# Nixieclock.net
KiCad netlist of a schematic drawn in EAGLE
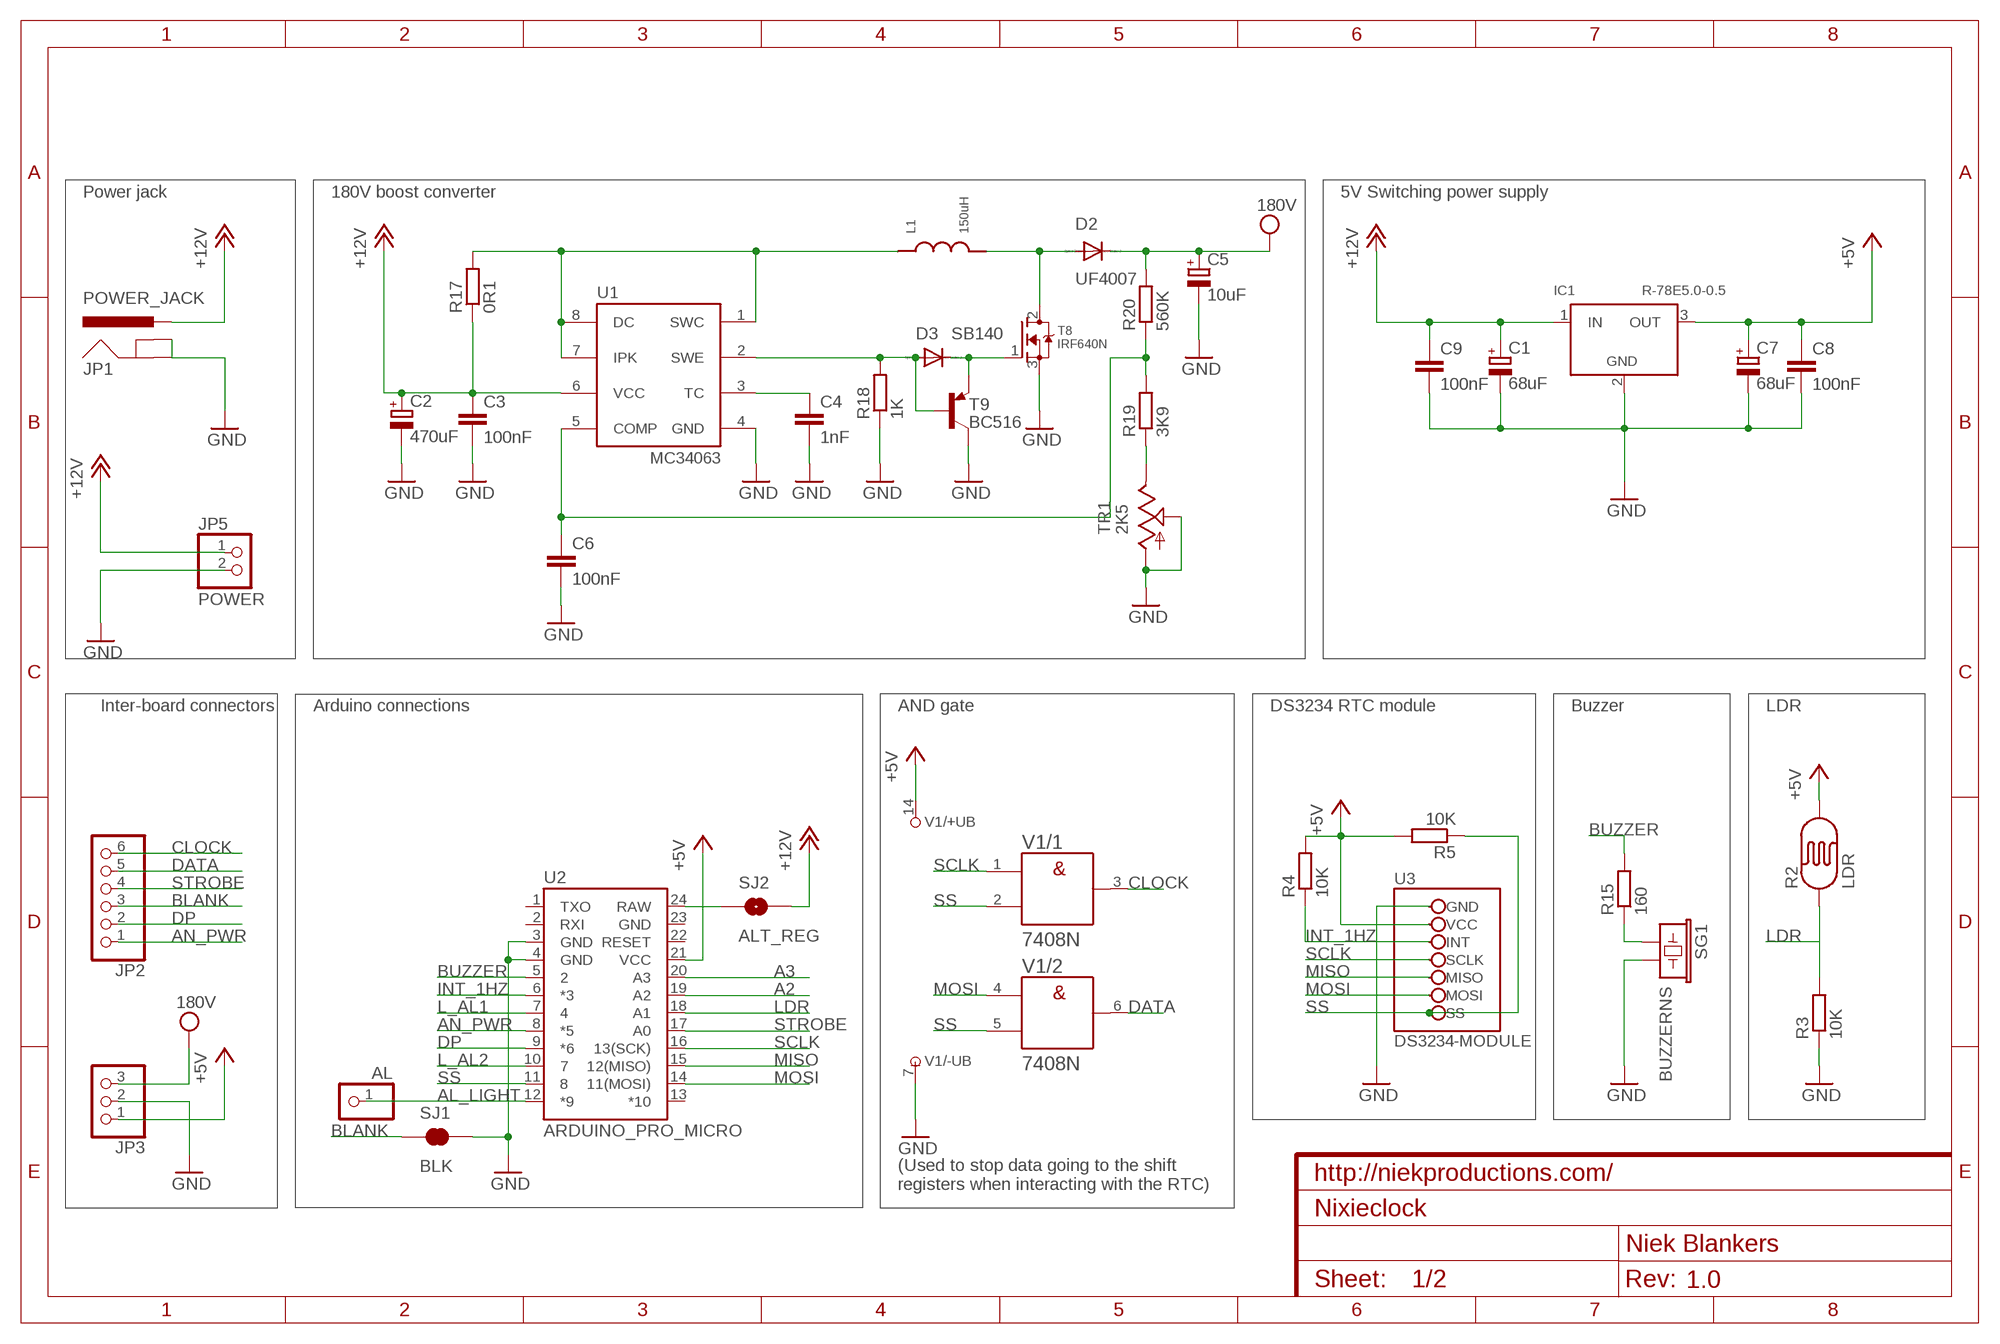
[diagram p0: schematic, sheet 1]
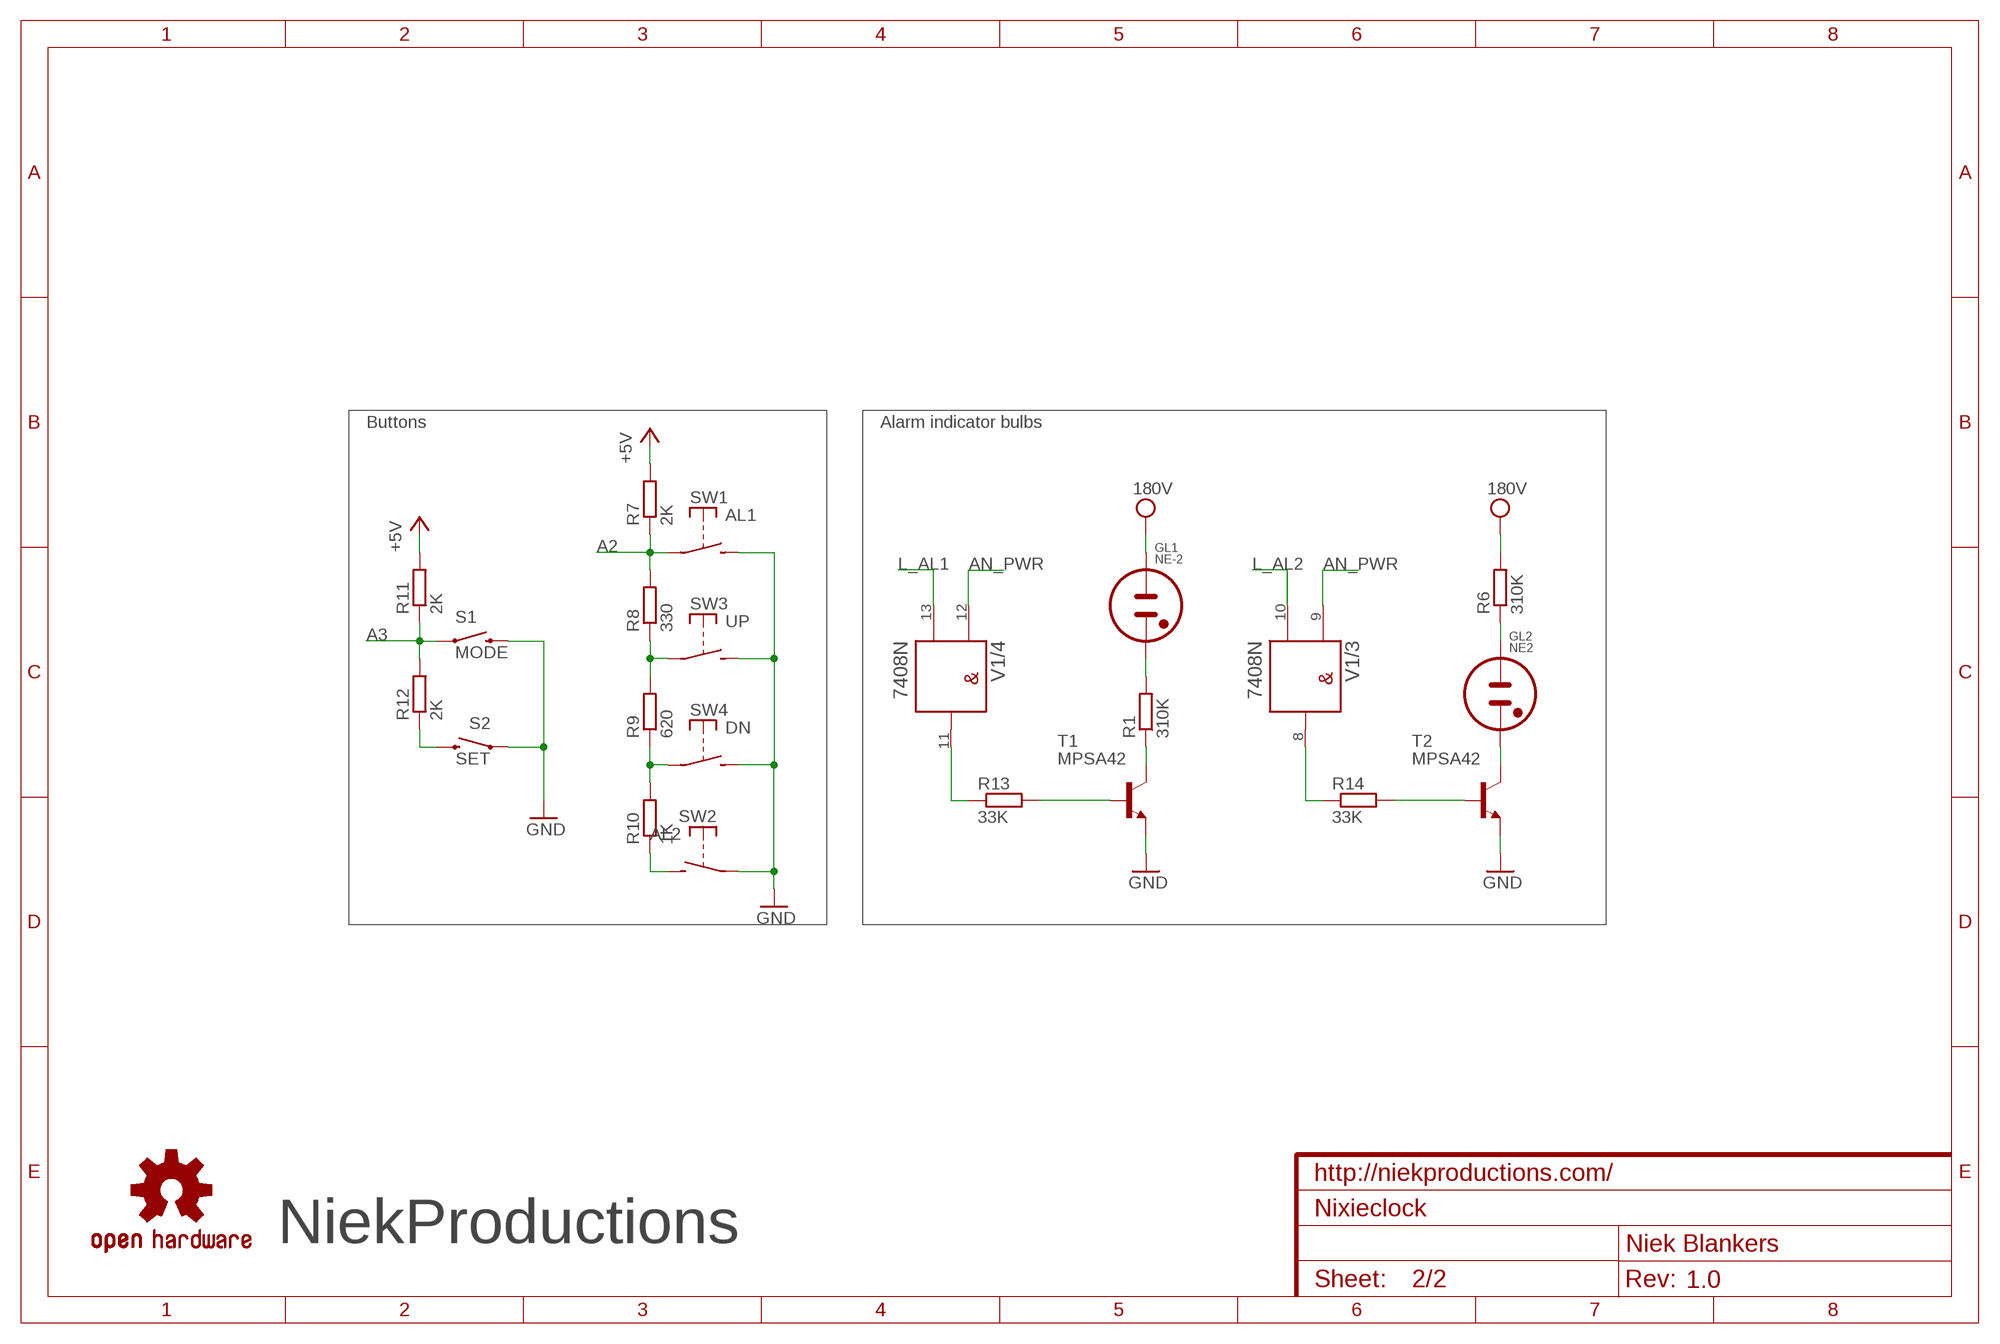
[diagram p1: schematic, sheet 2]

(export (version "E")
  (design (tool "Eeschema 10.0.6"))
  (components
    (comp (ref "AL")
      (value "PINHD-1X1")
      (footprint "eagle-import:1X01")
      (libsource (lib "eagle-import") (part "PINHD-1X1"))
    )
    (comp (ref "C1")
      (value "68uF")
      (footprint "eagle-import:E2,5-6")
      (libsource (lib "eagle-import") (part "CPOL-EUE2.5-6"))
    )
    (comp (ref "C2")
      (value "470uF")
      (footprint "eagle-import:E5-10,5")
      (libsource (lib "eagle-import") (part "CPOL-EUE5-10.5"))
    )
    (comp (ref "C3")
      (value "100nF")
      (footprint "eagle-import:C025-024X044")
      (libsource (lib "eagle-import") (part "C-EU025-024X044"))
    )
    (comp (ref "C4")
      (value "1nF")
      (footprint "eagle-import:C025-024X044")
      (libsource (lib "eagle-import") (part "C-EU025-024X044"))
    )
    (comp (ref "C5")
      (value "10uF")
      (footprint "eagle-import:E5-10,5")
      (libsource (lib "eagle-import") (part "CPOL-EUE5-10.5"))
    )
    (comp (ref "C6")
      (value "100nF")
      (footprint "eagle-import:C025-024X044")
      (libsource (lib "eagle-import") (part "C-EU025-024X044"))
    )
    (comp (ref "C7")
      (value "68uF")
      (footprint "eagle-import:E2,5-6")
      (libsource (lib "eagle-import") (part "CPOL-EUE2.5-6"))
    )
    (comp (ref "C8")
      (value "100nF")
      (footprint "eagle-import:C025-025X050")
      (libsource (lib "eagle-import") (part "C-EU025-025X050"))
    )
    (comp (ref "C9")
      (value "100nF")
      (footprint "eagle-import:C025-025X050")
      (libsource (lib "eagle-import") (part "C-EU025-025X050"))
    )
    (comp (ref "D2")
      (value "UF4007")
      (footprint "eagle-import:DO41-10")
      (libsource (lib "eagle-import") (part "1N4933"))
    )
    (comp (ref "D3")
      (value "SB140")
      (footprint "eagle-import:DO41-10")
      (libsource (lib "eagle-import") (part "1N4004"))
    )
    (comp (ref "IC1")
      (value "R-78E5.0-0.5")
      (footprint "eagle-import:R-78E")
      (libsource (lib "eagle-import") (part "R-78E5.0-0.5"))
    )
    (comp (ref "JP1")
      (value "POWER_JACK")
      (footprint "eagle-import:POWER_JACK_PTH_LOCK")
      (libsource (lib "eagle-import") (part "POWER_JACKPTH_LOCK"))
    )
    (comp (ref "JP2")
      (value "PINHD-1X6")
      (footprint "eagle-import:1X06")
      (libsource (lib "eagle-import") (part "PINHD-1X6"))
    )
    (comp (ref "JP3")
      (value "PINHD-1X3")
      (footprint "eagle-import:1X03")
      (libsource (lib "eagle-import") (part "PINHD-1X3"))
    )
    (comp (ref "JP5")
      (value "POWER")
      (footprint "eagle-import:1X02")
      (libsource (lib "eagle-import") (part "PINHD-1X2"))
    )
    (comp (ref "L1")
      (value "150uH")
      (footprint "eagle-import:INDUCTOR")
      (libsource (lib "eagle-import") (part "INDUCTOR"))
    )
    (comp (ref "R2")
      (value "LDR")
      (footprint "eagle-import:PHOTOCELL")
      (libsource (lib "eagle-import") (part "PHOTOCELLPTH"))
    )
    (comp (ref "R3")
      (value "10K")
      (footprint "eagle-import:0204_7")
      (libsource (lib "eagle-import") (part "R-EU_0204/7"))
    )
    (comp (ref "R4")
      (value "10K")
      (footprint "eagle-import:0204_7")
      (libsource (lib "eagle-import") (part "R-EU_0204/7"))
    )
    (comp (ref "R5")
      (value "10K")
      (footprint "eagle-import:0204_7")
      (libsource (lib "eagle-import") (part "R-EU_0204/7"))
    )
    (comp (ref "R15")
      (value "160")
      (footprint "eagle-import:0204_7")
      (libsource (lib "eagle-import") (part "R-EU_0204/7"))
    )
    (comp (ref "R17")
      (value "0R1")
      (footprint "eagle-import:0309_12")
      (libsource (lib "eagle-import") (part "R-EU_0309/12"))
    )
    (comp (ref "R18")
      (value "1K")
      (footprint "eagle-import:0207_10")
      (libsource (lib "eagle-import") (part "R-EU_0207/10"))
    )
    (comp (ref "R19")
      (value "3K9")
      (footprint "eagle-import:0207_10")
      (libsource (lib "eagle-import") (part "R-EU_0207/10"))
    )
    (comp (ref "R20")
      (value "560K")
      (footprint "eagle-import:0207_10")
      (libsource (lib "eagle-import") (part "R-EU_0207/10"))
    )
    (comp (ref "SG1")
      (value "BUZZERNS")
      (footprint "eagle-import:BUZZER-12MM-NS")
      (libsource (lib "eagle-import") (part "BUZZERNS"))
    )
    (comp (ref "SJ1")
      (value "BLK")
      (footprint "eagle-import:PAD-JUMPER-2-NC_BY_TRACE_YES_SILK")
      (libsource (lib "eagle-import") (part "JUMPER-PAD-2-NC_BY_TRACE"))
    )
    (comp (ref "SJ2")
      (value "ALT_REG")
      (footprint "eagle-import:SJ_2S-NO")
      (libsource (lib "eagle-import") (part "SOLDERJUMPERNO"))
    )
    (comp (ref "T8")
      (value "IRF640N")
      (footprint "eagle-import:TO220V")
      (libsource (lib "eagle-import") (part "MOSFET-NGDS_TO220V"))
    )
    (comp (ref "T9")
      (value "BC516")
      (footprint "eagle-import:TO92-EBC")
      (libsource (lib "eagle-import") (part "BC516"))
    )
    (comp (ref "TR1")
      (value "2K5")
      (footprint "eagle-import:6MM")
      (libsource (lib "eagle-import") (part "TRIM"))
    )
    (comp (ref "U1")
      (value "MC34063")
      (footprint "eagle-import:DIL08")
      (libsource (lib "eagle-import") (part "MC33063/MC34063P"))
    )
    (comp (ref "U2")
      (value "ARDUINO_PRO_MICRO")
      (footprint "eagle-import:ARDUINO_PRO_MICRO")
      (libsource (lib "eagle-import") (part "ARDUINO_PRO_MICRO"))
    )
    (comp (ref "U3")
      (value "DS3234-MODULE")
      (footprint "eagle-import:GEETECH-DS3234")
      (libsource (lib "eagle-import") (part "DS3234-MODULE"))
    )
    (comp (ref "V1")
      (value "7408N")
      (footprint "eagle-import:DIL14")
      (libsource (lib "eagle-import") (part "7408N"))
    )
    (comp (ref "GL1")
      (value "NE-2")
      (footprint "eagle-import:NE2-NEON-BULB-DRILL")
      (libsource (lib "eagle-import") (part "NE2-NEON-BULB-DRILL"))
    )
    (comp (ref "GL2")
      (value "NE2")
      (footprint "eagle-import:NE2-NEON-BULB-DRILL")
      (libsource (lib "eagle-import") (part "NE2-NEON-BULB-DRILL"))
    )
    (comp (ref "LOGO2")
      (value "OSHW-LOGOL")
      (footprint "eagle-import:OSHW-LOGO-L")
      (libsource (lib "eagle-import") (part "OSHW-LOGOL"))
    )
    (comp (ref "R1")
      (value "310K")
      (footprint "eagle-import:0204V")
      (libsource (lib "eagle-import") (part "R-EU_0204/2V"))
    )
    (comp (ref "R6")
      (value "310K")
      (footprint "eagle-import:0204_7")
      (libsource (lib "eagle-import") (part "R-EU_0204/7"))
    )
    (comp (ref "R7")
      (value "2K")
      (footprint "eagle-import:0204_7")
      (libsource (lib "eagle-import") (part "R-EU_0204/7"))
    )
    (comp (ref "R8")
      (value "330")
      (footprint "eagle-import:0204V")
      (libsource (lib "eagle-import") (part "R-EU_0204/2V"))
    )
    (comp (ref "R9")
      (value "620")
      (footprint "eagle-import:0204V")
      (libsource (lib "eagle-import") (part "R-EU_0204/2V"))
    )
    (comp (ref "R10")
      (value "1K")
      (footprint "eagle-import:0204V")
      (libsource (lib "eagle-import") (part "R-EU_0204/2V"))
    )
    (comp (ref "R11")
      (value "2K")
      (footprint "eagle-import:0204_7")
      (libsource (lib "eagle-import") (part "R-EU_0204/7"))
    )
    (comp (ref "R12")
      (value "2K")
      (footprint "eagle-import:0204_7")
      (libsource (lib "eagle-import") (part "R-EU_0204/7"))
    )
    (comp (ref "R13")
      (value "33K")
      (footprint "eagle-import:0204_7")
      (libsource (lib "eagle-import") (part "R-EU_0204/7"))
    )
    (comp (ref "R14")
      (value "33K")
      (footprint "eagle-import:0204_7")
      (libsource (lib "eagle-import") (part "R-EU_0204/7"))
    )
    (comp (ref "S1")
      (value "MODE")
      (footprint "eagle-import:TACTILE-PTH-SIDEEZ")
      (libsource (lib "eagle-import") (part "SWITCH-MOMENTARY-2SIDE_EZ"))
    )
    (comp (ref "S2")
      (value "SET")
      (footprint "eagle-import:TACTILE-PTH-SIDEEZ")
      (libsource (lib "eagle-import") (part "SWITCH-MOMENTARY-2SIDE_EZ"))
    )
    (comp (ref "SW1")
      (value "AL1")
      (footprint "eagle-import:SW-12.65MM-SQ-WHITE")
      (libsource (lib "eagle-import") (part "TACTILE-SQ12.65MM-WHITE"))
    )
    (comp (ref "SW2")
      (value "AL2")
      (footprint "eagle-import:SW-12.65MM-SQ-WHITE")
      (libsource (lib "eagle-import") (part "TACTILE-SQ12.65MM-WHITE"))
    )
    (comp (ref "SW3")
      (value "UP")
      (footprint "eagle-import:SW-12.65MM-SQ-WHITE")
      (libsource (lib "eagle-import") (part "TACTILE-SQ12.65MM-WHITE"))
    )
    (comp (ref "SW4")
      (value "DN")
      (footprint "eagle-import:SW-12.65MM-SQ-WHITE")
      (libsource (lib "eagle-import") (part "TACTILE-SQ12.65MM-WHITE"))
    )
    (comp (ref "T1")
      (value "MPSA42")
      (footprint "eagle-import:TO92-EBC")
      (libsource (lib "eagle-import") (part "-NPN-TO92-EBCMPSA42"))
    )
    (comp (ref "T2")
      (value "MPSA42")
      (footprint "eagle-import:TO92-EBC")
      (libsource (lib "eagle-import") (part "-NPN-TO92-EBCMPSA42"))
    )
    (comp (ref "U$4")
      (value "NPLOGO1CM-DIA")
      (footprint "eagle-import:NPLOGO-1CM")
      (libsource (lib "eagle-import") (part "NPLOGO1CM-DIA"))
    )
  )
  (nets
    (net (code "1") (name "+5V") (class "Default")
      (node (ref "C7") (pin "+") (pinfunction "+_+") (pintype "passive"))
      (node (ref "C8") (pin "1") (pinfunction "1_1") (pintype "passive"))
      (node (ref "IC1") (pin "3") (pinfunction "OUT_3") (pintype "output"))
      (node (ref "JP3") (pin "1") (pinfunction "1_1") (pintype "passive"))
      (node (ref "R11") (pin "2") (pinfunction "2_2") (pintype "passive"))
      (node (ref "R2") (pin "2") (pinfunction "P$2_2") (pintype "bidirectional"))
      (node (ref "R4") (pin "2") (pinfunction "2_2") (pintype "passive"))
      (node (ref "R5") (pin "2") (pinfunction "2_2") (pintype "passive"))
      (node (ref "R7") (pin "2") (pinfunction "2_2") (pintype "passive"))
      (node (ref "U2") (pin "21") (pinfunction "VCC_21") (pintype "bidirectional"))
      (node (ref "U3") (pin "VCC") (pinfunction "VCC_VCC") (pintype "input"))
      (node (ref "V1") (pin "14") (pinfunction "+UB_14") (pintype "power_in"))
    )
    (net (code "2") (name "+12V") (class "Default")
      (node (ref "C1") (pin "+") (pinfunction "+_+") (pintype "passive"))
      (node (ref "C2") (pin "+") (pinfunction "+_+") (pintype "passive"))
      (node (ref "C3") (pin "1") (pinfunction "1_1") (pintype "passive"))
      (node (ref "C9") (pin "1") (pinfunction "1_1") (pintype "passive"))
      (node (ref "IC1") (pin "1") (pinfunction "IN_1") (pintype "input"))
      (node (ref "JP1") (pin "PWR") (pinfunction "PWR_PWR") (pintype "bidirectional"))
      (node (ref "JP5") (pin "1") (pinfunction "1_1") (pintype "passive"))
      (node (ref "R17") (pin "1") (pinfunction "1_1") (pintype "passive"))
      (node (ref "SJ2") (pin "2") (pinfunction "2_2") (pintype "passive"))
      (node (ref "U1") (pin "6") (pinfunction "VCC_6") (pintype "power_in"))
    )
    (net (code "3") (name "A2") (class "Default")
      (node (ref "R7") (pin "1") (pinfunction "1_1") (pintype "passive"))
      (node (ref "R8") (pin "2") (pinfunction "2_2") (pintype "passive"))
      (node (ref "SW1") (pin "SW-CENTER") (pinfunction "P_SW-CENTER") (pintype "passive"))
      (node (ref "U2") (pin "19") (pinfunction "A2_19") (pintype "bidirectional"))
    )
    (net (code "4") (name "A3") (class "Default")
      (node (ref "R11") (pin "1") (pinfunction "1_1") (pintype "passive"))
      (node (ref "R12") (pin "2") (pinfunction "2_2") (pintype "passive"))
      (node (ref "S1") (pin "1") (pinfunction "1_1") (pintype "passive"))
      (node (ref "U2") (pin "20") (pinfunction "A3_20") (pintype "bidirectional"))
    )
    (net (code "5") (name "AL_LIGHT") (class "Default")
      (node (ref "AL") (pin "1") (pinfunction "1_1") (pintype "passive"))
      (node (ref "U2") (pin "12") (pinfunction "*9_12") (pintype "bidirectional"))
    )
    (net (code "6") (name "AN_PWR") (class "Default")
      (node (ref "JP2") (pin "1") (pinfunction "1_1") (pintype "passive"))
      (node (ref "U2") (pin "8") (pinfunction "*5_8") (pintype "bidirectional"))
      (node (ref "V1") (pin "12") (pinfunction "A_12") (pintype "input"))
      (node (ref "V1") (pin "9") (pinfunction "A_9") (pintype "input"))
    )
    (net (code "7") (name "BLANK") (class "Default")
      (node (ref "JP2") (pin "3") (pinfunction "3_3") (pintype "passive"))
      (node (ref "SJ1") (pin "1") (pinfunction "1_1") (pintype "passive"))
    )
    (net (code "8") (name "BUZZER") (class "Default")
      (node (ref "R15") (pin "2") (pinfunction "2_2") (pintype "passive"))
      (node (ref "U2") (pin "5") (pinfunction "2_5") (pintype "bidirectional"))
    )
    (net (code "9") (name "CLOCK") (class "Default")
      (node (ref "JP2") (pin "6") (pinfunction "6_6") (pintype "passive"))
      (node (ref "V1") (pin "3") (pinfunction "Y_3") (pintype "output"))
    )
    (net (code "10") (name "DATA") (class "Default")
      (node (ref "JP2") (pin "5") (pinfunction "5_5") (pintype "passive"))
      (node (ref "V1") (pin "6") (pinfunction "Y_6") (pintype "output"))
    )
    (net (code "11") (name "DP") (class "Default")
      (node (ref "JP2") (pin "2") (pinfunction "2_2") (pintype "passive"))
      (node (ref "U2") (pin "9") (pinfunction "*6_9") (pintype "bidirectional"))
    )
    (net (code "12") (name "GND") (class "Default")
      (node (ref "C1") (pin "-") (pinfunction "-_-") (pintype "passive"))
      (node (ref "C2") (pin "-") (pinfunction "-_-") (pintype "passive"))
      (node (ref "C3") (pin "2") (pinfunction "2_2") (pintype "passive"))
      (node (ref "C4") (pin "2") (pinfunction "2_2") (pintype "passive"))
      (node (ref "C5") (pin "-") (pinfunction "-_-") (pintype "passive"))
      (node (ref "C6") (pin "2") (pinfunction "2_2") (pintype "passive"))
      (node (ref "C7") (pin "-") (pinfunction "-_-") (pintype "passive"))
      (node (ref "C8") (pin "2") (pinfunction "2_2") (pintype "passive"))
      (node (ref "C9") (pin "2") (pinfunction "2_2") (pintype "passive"))
      (node (ref "IC1") (pin "2") (pinfunction "GND_2") (pintype "power_in"))
      (node (ref "JP1") (pin "GND") (pinfunction "GND_GND") (pintype "bidirectional"))
      (node (ref "JP1") (pin "GNDBREAK") (pinfunction "GNDBREAK_GNDBREAK") (pintype "bidirectional"))
      (node (ref "JP3") (pin "2") (pinfunction "2_2") (pintype "passive"))
      (node (ref "JP5") (pin "2") (pinfunction "2_2") (pintype "passive"))
      (node (ref "R18") (pin "1") (pinfunction "1_1") (pintype "passive"))
      (node (ref "R3") (pin "1") (pinfunction "1_1") (pintype "passive"))
      (node (ref "S1") (pin "2") (pinfunction "2_2") (pintype "passive"))
      (node (ref "S2") (pin "1") (pinfunction "1_1") (pintype "passive"))
      (node (ref "SG1") (pin "-") (pinfunction "2_-") (pintype "passive"))
      (node (ref "SG1") (pin "--") (pinfunction "2_--") (pintype "passive"))
      (node (ref "SJ1") (pin "2") (pinfunction "2_2") (pintype "passive"))
      (node (ref "SW1") (pin "SW-OUTSIDE") (pinfunction "S_SW-OUTSIDE") (pintype "passive"))
      (node (ref "SW2") (pin "SW-CENTER") (pinfunction "P_SW-CENTER") (pintype "passive"))
      (node (ref "SW3") (pin "SW-OUTSIDE") (pinfunction "S_SW-OUTSIDE") (pintype "passive"))
      (node (ref "SW4") (pin "SW-OUTSIDE") (pinfunction "S_SW-OUTSIDE") (pintype "passive"))
      (node (ref "T1") (pin "E") (pinfunction "E_E") (pintype "passive"))
      (node (ref "T2") (pin "E") (pinfunction "E_E") (pintype "passive"))
      (node (ref "T8") (pin "3") (pinfunction "S_3") (pintype "bidirectional"))
      (node (ref "T9") (pin "C") (pinfunction "C_C") (pintype "passive"))
      (node (ref "TR1") (pin "A") (pinfunction "A_A") (pintype "passive"))
      (node (ref "TR1") (pin "S") (pinfunction "S_S") (pintype "passive"))
      (node (ref "U1") (pin "4") (pinfunction "GND_4") (pintype "power_in"))
      (node (ref "U2") (pin "3") (pinfunction "GND_3") (pintype "bidirectional"))
      (node (ref "U2") (pin "4") (pinfunction "GND_4") (pintype "bidirectional"))
      (node (ref "U3") (pin "GND~1") (pinfunction "GND_GND~1") (pintype "power_in"))
      (node (ref "U3") (pin "GND~2") (pinfunction "GND_GND~2") (pintype "power_in"))
      (node (ref "V1") (pin "7") (pinfunction "-UB_7") (pintype "power_in"))
    )
    (net (code "13") (name "INT_1HZ") (class "Default")
      (node (ref "R4") (pin "1") (pinfunction "1_1") (pintype "passive"))
      (node (ref "U2") (pin "6") (pinfunction "*3_6") (pintype "bidirectional"))
      (node (ref "U3") (pin "INT") (pinfunction "INT_INT") (pintype "bidirectional"))
    )
    (net (code "14") (name "LDR") (class "Default")
      (node (ref "R2") (pin "1") (pinfunction "P$1_1") (pintype "bidirectional"))
      (node (ref "R3") (pin "2") (pinfunction "2_2") (pintype "passive"))
      (node (ref "U2") (pin "18") (pinfunction "A1_18") (pintype "bidirectional"))
    )
    (net (code "15") (name "L_AL1") (class "Default")
      (node (ref "U2") (pin "7") (pinfunction "4_7") (pintype "bidirectional"))
      (node (ref "V1") (pin "13") (pinfunction "B_13") (pintype "input"))
    )
    (net (code "16") (name "L_AL2") (class "Default")
      (node (ref "U2") (pin "10") (pinfunction "7_10") (pintype "bidirectional"))
      (node (ref "V1") (pin "10") (pinfunction "B_10") (pintype "input"))
    )
    (net (code "17") (name "MISO") (class "Default")
      (node (ref "U2") (pin "15") (pinfunction "12(MISO)_15") (pintype "bidirectional"))
      (node (ref "U3") (pin "MISO") (pinfunction "MISO_MISO") (pintype "bidirectional"))
    )
    (net (code "18") (name "MOSI") (class "Default")
      (node (ref "U2") (pin "14") (pinfunction "11(MOSI)_14") (pintype "bidirectional"))
      (node (ref "U3") (pin "MOSI") (pinfunction "MOSI_MOSI") (pintype "bidirectional"))
      (node (ref "V1") (pin "4") (pinfunction "A_4") (pintype "input"))
    )
    (net (code "19") (name "Net-(GL1-A1)") (class "Default")
      (node (ref "GL1") (pin "2") (pinfunction "A1_2") (pintype "passive"))
      (node (ref "R1") (pin "2") (pinfunction "2_2") (pintype "passive"))
    )
    (net (code "20") (name "Net-(GL2-A)") (class "Default")
      (node (ref "GL2") (pin "1") (pinfunction "A_1") (pintype "passive"))
      (node (ref "R6") (pin "1") (pinfunction "1_1") (pintype "passive"))
    )
    (net (code "21") (name "Net-(GL2-A1)") (class "Default")
      (node (ref "GL2") (pin "2") (pinfunction "A1_2") (pintype "passive"))
      (node (ref "T2") (pin "C") (pinfunction "C_C") (pintype "passive"))
    )
    (net (code "22") (name "Net-(R1-Pad1)") (class "Default")
      (node (ref "R1") (pin "1") (pinfunction "1_1") (pintype "passive"))
      (node (ref "T1") (pin "C") (pinfunction "C_C") (pintype "passive"))
    )
    (net (code "23") (name "Net-(R12-Pad1)") (class "Default")
      (node (ref "R12") (pin "1") (pinfunction "1_1") (pintype "passive"))
      (node (ref "S2") (pin "2") (pinfunction "2_2") (pintype "passive"))
    )
    (net (code "24") (name "Net-(R13-Pad2)") (class "Default")
      (node (ref "R13") (pin "2") (pinfunction "2_2") (pintype "passive"))
      (node (ref "T1") (pin "B") (pinfunction "B_B") (pintype "passive"))
    )
    (net (code "25") (name "Net-(R14-Pad2)") (class "Default")
      (node (ref "R14") (pin "2") (pinfunction "2_2") (pintype "passive"))
      (node (ref "T2") (pin "B") (pinfunction "B_B") (pintype "passive"))
    )
    (net (code "26") (name "Net-(R19-Pad1)") (class "Default")
      (node (ref "R19") (pin "1") (pinfunction "1_1") (pintype "passive"))
      (node (ref "TR1") (pin "E") (pinfunction "E_E") (pintype "passive"))
    )
    (net (code "27") (name "Net-(SG1-1)") (class "Default")
      (node (ref "R15") (pin "1") (pinfunction "1_1") (pintype "passive"))
      (node (ref "SG1") (pin "+") (pinfunction "1_+") (pintype "passive"))
    )
    (net (code "28") (name "Net-(SW2-S)") (class "Default")
      (node (ref "R10") (pin "1") (pinfunction "1_1") (pintype "passive"))
      (node (ref "SW2") (pin "SW-OUTSIDE") (pinfunction "S_SW-OUTSIDE") (pintype "passive"))
    )
    (net (code "29") (name "Net-(SW3-P)") (class "Default")
      (node (ref "R8") (pin "1") (pinfunction "1_1") (pintype "passive"))
      (node (ref "R9") (pin "2") (pinfunction "2_2") (pintype "passive"))
      (node (ref "SW3") (pin "SW-CENTER") (pinfunction "P_SW-CENTER") (pintype "passive"))
    )
    (net (code "30") (name "Net-(SW4-P)") (class "Default")
      (node (ref "R10") (pin "2") (pinfunction "2_2") (pintype "passive"))
      (node (ref "R9") (pin "1") (pinfunction "1_1") (pintype "passive"))
      (node (ref "SW4") (pin "SW-CENTER") (pinfunction "P_SW-CENTER") (pintype "passive"))
    )
    (net (code "31") (name "Net-(T8-D)") (class "Default")
      (node (ref "D2") (pin "A") (pinfunction "A_A") (pintype "passive"))
      (node (ref "L1") (pin "P$2") (pinfunction "P$2_P$2") (pintype "bidirectional"))
      (node (ref "T8") (pin "2") (pinfunction "D_2") (pintype "bidirectional"))
    )
    (net (code "32") (name "Net-(T8-G)") (class "Default")
      (node (ref "D3") (pin "C") (pinfunction "C_C") (pintype "passive"))
      (node (ref "T8") (pin "1") (pinfunction "G_1") (pintype "bidirectional"))
      (node (ref "T9") (pin "E") (pinfunction "E_E") (pintype "passive"))
    )
    (net (code "33") (name "Net-(U1-COMP)") (class "Default")
      (node (ref "C6") (pin "1") (pinfunction "1_1") (pintype "passive"))
      (node (ref "R19") (pin "2") (pinfunction "2_2") (pintype "passive"))
      (node (ref "R20") (pin "1") (pinfunction "1_1") (pintype "passive"))
      (node (ref "U1") (pin "5") (pinfunction "COMP_5") (pintype "input"))
    )
    (net (code "34") (name "Net-(U1-DC)") (class "Default")
      (node (ref "L1") (pin "P$1") (pinfunction "P$1_P$1") (pintype "bidirectional"))
      (node (ref "R17") (pin "2") (pinfunction "2_2") (pintype "passive"))
      (node (ref "U1") (pin "1") (pinfunction "SWC_1") (pintype "input"))
      (node (ref "U1") (pin "7") (pinfunction "IPK_7") (pintype "bidirectional"))
      (node (ref "U1") (pin "8") (pinfunction "DC_8") (pintype "input"))
    )
    (net (code "35") (name "Net-(U1-SWE)") (class "Default")
      (node (ref "D3") (pin "A") (pinfunction "A_A") (pintype "passive"))
      (node (ref "R18") (pin "2") (pinfunction "2_2") (pintype "passive"))
      (node (ref "T9") (pin "B") (pinfunction "B_B") (pintype "passive"))
      (node (ref "U1") (pin "2") (pinfunction "SWE_2") (pintype "input"))
    )
    (net (code "36") (name "Net-(U1-TC)") (class "Default")
      (node (ref "C4") (pin "1") (pinfunction "1_1") (pintype "passive"))
      (node (ref "U1") (pin "3") (pinfunction "TC_3") (pintype "input"))
    )
    (net (code "37") (name "Net-(U2-RAW)") (class "Default")
      (node (ref "SJ2") (pin "1") (pinfunction "1_1") (pintype "passive"))
      (node (ref "U2") (pin "24") (pinfunction "RAW_24") (pintype "bidirectional"))
    )
    (net (code "38") (name "Net-(V1E-Y)") (class "Default")
      (node (ref "R14") (pin "1") (pinfunction "1_1") (pintype "passive"))
      (node (ref "V1") (pin "8") (pinfunction "Y_8") (pintype "output"))
    )
    (net (code "39") (name "Net-(V1F-Y)") (class "Default")
      (node (ref "R13") (pin "1") (pinfunction "1_1") (pintype "passive"))
      (node (ref "V1") (pin "11") (pinfunction "Y_11") (pintype "output"))
    )
    (net (code "40") (name "SCLK") (class "Default")
      (node (ref "U2") (pin "16") (pinfunction "13(SCK)_16") (pintype "bidirectional"))
      (node (ref "U3") (pin "SCLK") (pinfunction "SCLK_SCLK") (pintype "bidirectional"))
      (node (ref "V1") (pin "1") (pinfunction "A_1") (pintype "input"))
    )
    (net (code "41") (name "SS") (class "Default")
      (node (ref "R5") (pin "1") (pinfunction "1_1") (pintype "passive"))
      (node (ref "U2") (pin "11") (pinfunction "8_11") (pintype "bidirectional"))
      (node (ref "U3") (pin "SS") (pinfunction "SS_SS") (pintype "bidirectional"))
      (node (ref "V1") (pin "2") (pinfunction "B_2") (pintype "input"))
      (node (ref "V1") (pin "5") (pinfunction "B_5") (pintype "input"))
    )
    (net (code "42") (name "STROBE") (class "Default")
      (node (ref "JP2") (pin "4") (pinfunction "4_4") (pintype "passive"))
      (node (ref "U2") (pin "17") (pinfunction "A0_17") (pintype "bidirectional"))
    )
    (net (code "43") (name "VPP") (class "Default")
      (node (ref "C5") (pin "+") (pinfunction "+_+") (pintype "passive"))
      (node (ref "D2") (pin "C") (pinfunction "C_C") (pintype "passive"))
      (node (ref "GL1") (pin "1") (pinfunction "A_1") (pintype "passive"))
      (node (ref "JP3") (pin "3") (pinfunction "3_3") (pintype "passive"))
      (node (ref "R20") (pin "2") (pinfunction "2_2") (pintype "passive"))
      (node (ref "R6") (pin "2") (pinfunction "2_2") (pintype "passive"))
    )
    (net (code "44") (name "unconnected-(U2-*10-Pad13)") (class "Default")
      (node (ref "U2") (pin "13") (pinfunction "*10_13") (pintype "bidirectional"))
    )
    (net (code "45") (name "unconnected-(U2-GND-Pad23)") (class "Default")
      (node (ref "U2") (pin "23") (pinfunction "GND_23") (pintype "bidirectional"))
    )
    (net (code "46") (name "unconnected-(U2-RESET-Pad22)") (class "Default")
      (node (ref "U2") (pin "22") (pinfunction "RESET_22") (pintype "bidirectional"))
    )
    (net (code "47") (name "unconnected-(U2-RXI-Pad2)") (class "Default")
      (node (ref "U2") (pin "2") (pinfunction "RXI_2") (pintype "bidirectional"))
    )
    (net (code "48") (name "unconnected-(U2-TXO-Pad1)") (class "Default")
      (node (ref "U2") (pin "1") (pinfunction "TXO_1") (pintype "bidirectional"))
    )
  )
)
